# dot_matrix_4A_noGND.net
KiCad netlist of a schematic drawn in EAGLE
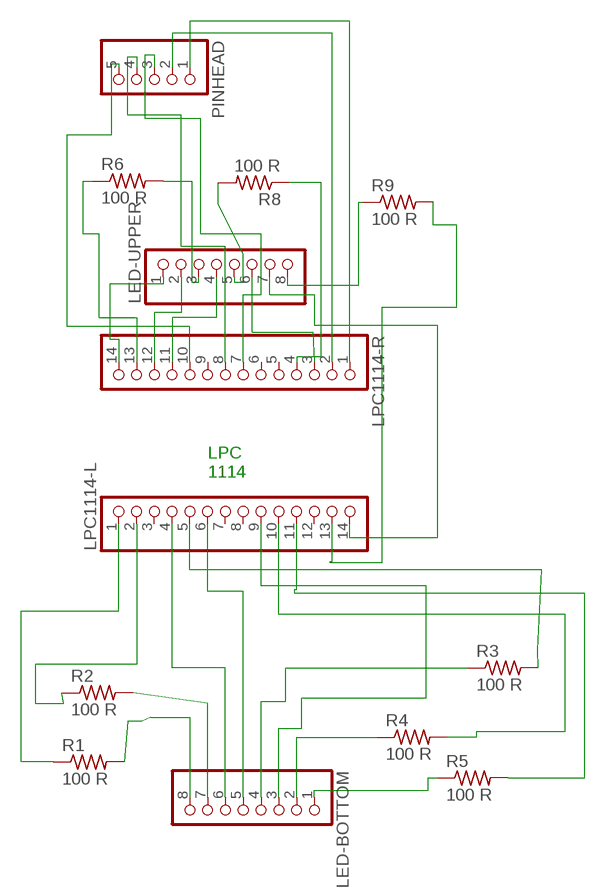
[diagram p0: schematic, sheet 1]

(export (version "E")
  (design (tool "Eeschema 10.0.6"))
  (components
    (comp (ref "LED-BOTTOM")
      (value "PINHD-1X8")
      (footprint "eagle-import:1X08")
      (libsource (lib "eagle-import") (part "PINHD-1X8"))
    )
    (comp (ref "LED-UPPER")
      (value "PINHD-1X8")
      (footprint "eagle-import:1X08")
      (libsource (lib "eagle-import") (part "PINHD-1X8"))
    )
    (comp (ref "LPC1114-L")
      (value "PINHD-1X14")
      (footprint "eagle-import:1X14")
      (libsource (lib "eagle-import") (part "PINHD-1X14"))
    )
    (comp (ref "LPC1114-R")
      (value "PINHD-1X14")
      (footprint "eagle-import:1X14")
      (libsource (lib "eagle-import") (part "PINHD-1X14"))
    )
    (comp (ref "PINHEAD")
      (value "PINHD-1X5")
      (footprint "eagle-import:1X05")
      (libsource (lib "eagle-import") (part "PINHD-1X5"))
    )
    (comp (ref "R1")
      (value "100 R")
      (footprint "eagle-import:0204_7")
      (libsource (lib "eagle-import") (part "R-US_0204/7"))
    )
    (comp (ref "R2")
      (value "100 R")
      (footprint "eagle-import:0204_7")
      (libsource (lib "eagle-import") (part "R-US_0204/7"))
    )
    (comp (ref "R3")
      (value "100 R")
      (footprint "eagle-import:0204_7")
      (libsource (lib "eagle-import") (part "R-US_0204/7"))
    )
    (comp (ref "R4")
      (value "100 R")
      (footprint "eagle-import:0204_7")
      (libsource (lib "eagle-import") (part "R-US_0204/7"))
    )
    (comp (ref "R5")
      (value "100 R")
      (footprint "eagle-import:0204_7")
      (libsource (lib "eagle-import") (part "R-US_0204/7"))
    )
    (comp (ref "R6")
      (value "100 R")
      (footprint "eagle-import:0204_7")
      (libsource (lib "eagle-import") (part "R-US_0204/7"))
    )
    (comp (ref "R8")
      (value "100 R")
      (footprint "eagle-import:0204_7")
      (libsource (lib "eagle-import") (part "R-US_0204/7"))
    )
    (comp (ref "R9")
      (value "100 R")
      (footprint "eagle-import:0204_7")
      (libsource (lib "eagle-import") (part "R-US_0204/7"))
    )
  )
  (nets
    (net (code "1") (name "Net-(LED-BOTTOM-Pad1)") (class "Default")
      (node (ref "LED-BOTTOM") (pin "1") (pinfunction "1_1") (pintype "passive"))
      (node (ref "R5") (pin "1") (pinfunction "1_1") (pintype "passive"))
    )
    (net (code "2") (name "Net-(LED-BOTTOM-Pad2)") (class "Default")
      (node (ref "LED-BOTTOM") (pin "2") (pinfunction "2_2") (pintype "passive"))
      (node (ref "R4") (pin "1") (pinfunction "1_1") (pintype "passive"))
    )
    (net (code "3") (name "Net-(LED-BOTTOM-Pad3)") (class "Default")
      (node (ref "LED-BOTTOM") (pin "3") (pinfunction "3_3") (pintype "passive"))
      (node (ref "LPC1114-L") (pin "9") (pinfunction "9_9") (pintype "passive"))
    )
    (net (code "4") (name "Net-(LED-BOTTOM-Pad4)") (class "Default")
      (node (ref "LED-BOTTOM") (pin "4") (pinfunction "4_4") (pintype "passive"))
      (node (ref "R3") (pin "1") (pinfunction "1_1") (pintype "passive"))
    )
    (net (code "5") (name "Net-(LED-BOTTOM-Pad5)") (class "Default")
      (node (ref "LED-BOTTOM") (pin "5") (pinfunction "5_5") (pintype "passive"))
      (node (ref "LPC1114-L") (pin "6") (pinfunction "6_6") (pintype "passive"))
    )
    (net (code "6") (name "Net-(LED-BOTTOM-Pad6)") (class "Default")
      (node (ref "LED-BOTTOM") (pin "6") (pinfunction "6_6") (pintype "passive"))
      (node (ref "LPC1114-L") (pin "4") (pinfunction "4_4") (pintype "passive"))
    )
    (net (code "7") (name "Net-(LED-BOTTOM-Pad7)") (class "Default")
      (node (ref "LED-BOTTOM") (pin "7") (pinfunction "7_7") (pintype "passive"))
      (node (ref "R2") (pin "2") (pinfunction "2_2") (pintype "passive"))
    )
    (net (code "8") (name "Net-(LED-BOTTOM-Pad8)") (class "Default")
      (node (ref "LED-BOTTOM") (pin "8") (pinfunction "8_8") (pintype "passive"))
      (node (ref "R1") (pin "2") (pinfunction "2_2") (pintype "passive"))
    )
    (net (code "9") (name "Net-(LED-UPPER-Pad1)") (class "Default")
      (node (ref "LED-UPPER") (pin "1") (pinfunction "1_1") (pintype "passive"))
      (node (ref "LPC1114-R") (pin "14") (pinfunction "14_14") (pintype "passive"))
    )
    (net (code "10") (name "Net-(LED-UPPER-Pad2)") (class "Default")
      (node (ref "LED-UPPER") (pin "2") (pinfunction "2_2") (pintype "passive"))
      (node (ref "LPC1114-R") (pin "12") (pinfunction "12_12") (pintype "passive"))
    )
    (net (code "11") (name "Net-(LED-UPPER-Pad3)") (class "Default")
      (node (ref "LED-UPPER") (pin "3") (pinfunction "3_3") (pintype "passive"))
      (node (ref "R6") (pin "2") (pinfunction "2_2") (pintype "passive"))
    )
    (net (code "12") (name "Net-(LED-UPPER-Pad4)") (class "Default")
      (node (ref "LED-UPPER") (pin "4") (pinfunction "4_4") (pintype "passive"))
      (node (ref "LPC1114-R") (pin "11") (pinfunction "11_11") (pintype "passive"))
    )
    (net (code "13") (name "Net-(LED-UPPER-Pad5)") (class "Default")
      (node (ref "LED-UPPER") (pin "5") (pinfunction "5_5") (pintype "passive"))
      (node (ref "R8") (pin "2") (pinfunction "2_2") (pintype "passive"))
    )
    (net (code "14") (name "Net-(LED-UPPER-Pad6)") (class "Default")
      (node (ref "LED-UPPER") (pin "6") (pinfunction "6_6") (pintype "passive"))
      (node (ref "LPC1114-R") (pin "3") (pinfunction "3_3") (pintype "passive"))
    )
    (net (code "15") (name "Net-(LED-UPPER-Pad7)") (class "Default")
      (node (ref "LED-UPPER") (pin "7") (pinfunction "7_7") (pintype "passive"))
      (node (ref "LPC1114-L") (pin "14") (pinfunction "14_14") (pintype "passive"))
    )
    (net (code "16") (name "Net-(LED-UPPER-Pad8)") (class "Default")
      (node (ref "LED-UPPER") (pin "8") (pinfunction "8_8") (pintype "passive"))
      (node (ref "R9") (pin "1") (pinfunction "1_1") (pintype "passive"))
    )
    (net (code "17") (name "Net-(LPC1114-L-Pad1)") (class "Default")
      (node (ref "LPC1114-L") (pin "1") (pinfunction "1_1") (pintype "passive"))
      (node (ref "R1") (pin "1") (pinfunction "1_1") (pintype "passive"))
    )
    (net (code "18") (name "Net-(LPC1114-L-Pad2)") (class "Default")
      (node (ref "LPC1114-L") (pin "2") (pinfunction "2_2") (pintype "passive"))
      (node (ref "R2") (pin "1") (pinfunction "1_1") (pintype "passive"))
    )
    (net (code "19") (name "Net-(LPC1114-L-Pad5)") (class "Default")
      (node (ref "LPC1114-L") (pin "5") (pinfunction "5_5") (pintype "passive"))
      (node (ref "R3") (pin "2") (pinfunction "2_2") (pintype "passive"))
    )
    (net (code "20") (name "Net-(LPC1114-L-Pad10)") (class "Default")
      (node (ref "LPC1114-L") (pin "10") (pinfunction "10_10") (pintype "passive"))
      (node (ref "R4") (pin "2") (pinfunction "2_2") (pintype "passive"))
    )
    (net (code "21") (name "Net-(LPC1114-L-Pad11)") (class "Default")
      (node (ref "LPC1114-L") (pin "11") (pinfunction "11_11") (pintype "passive"))
      (node (ref "R5") (pin "2") (pinfunction "2_2") (pintype "passive"))
    )
    (net (code "22") (name "Net-(LPC1114-L-Pad13)") (class "Default")
      (node (ref "LPC1114-L") (pin "13") (pinfunction "13_13") (pintype "passive"))
      (node (ref "R9") (pin "2") (pinfunction "2_2") (pintype "passive"))
    )
    (net (code "23") (name "Net-(LPC1114-R-Pad1)") (class "Default")
      (node (ref "LPC1114-R") (pin "1") (pinfunction "1_1") (pintype "passive"))
      (node (ref "PINHEAD") (pin "1") (pinfunction "1_1") (pintype "passive"))
    )
    (net (code "24") (name "Net-(LPC1114-R-Pad2)") (class "Default")
      (node (ref "LPC1114-R") (pin "2") (pinfunction "2_2") (pintype "passive"))
      (node (ref "PINHEAD") (pin "2") (pinfunction "2_2") (pintype "passive"))
    )
    (net (code "25") (name "Net-(LPC1114-R-Pad4)") (class "Default")
      (node (ref "LPC1114-R") (pin "4") (pinfunction "4_4") (pintype "passive"))
      (node (ref "R8") (pin "1") (pinfunction "1_1") (pintype "passive"))
    )
    (net (code "26") (name "Net-(LPC1114-R-Pad7)") (class "Default")
      (node (ref "LPC1114-R") (pin "7") (pinfunction "7_7") (pintype "passive"))
      (node (ref "PINHEAD") (pin "3") (pinfunction "3_3") (pintype "passive"))
    )
    (net (code "27") (name "Net-(LPC1114-R-Pad8)") (class "Default")
      (node (ref "LPC1114-R") (pin "8") (pinfunction "8_8") (pintype "passive"))
      (node (ref "PINHEAD") (pin "4") (pinfunction "4_4") (pintype "passive"))
    )
    (net (code "28") (name "Net-(LPC1114-R-Pad10)") (class "Default")
      (node (ref "LPC1114-R") (pin "10") (pinfunction "10_10") (pintype "passive"))
      (node (ref "PINHEAD") (pin "5") (pinfunction "5_5") (pintype "passive"))
    )
    (net (code "29") (name "Net-(LPC1114-R-Pad13)") (class "Default")
      (node (ref "LPC1114-R") (pin "13") (pinfunction "13_13") (pintype "passive"))
      (node (ref "R6") (pin "1") (pinfunction "1_1") (pintype "passive"))
    )
    (net (code "30") (name "unconnected-(LPC1114-L-Pad3)") (class "Default")
      (node (ref "LPC1114-L") (pin "3") (pinfunction "3_3") (pintype "passive"))
    )
    (net (code "31") (name "unconnected-(LPC1114-L-Pad7)") (class "Default")
      (node (ref "LPC1114-L") (pin "7") (pinfunction "7_7") (pintype "passive"))
    )
    (net (code "32") (name "unconnected-(LPC1114-L-Pad8)") (class "Default")
      (node (ref "LPC1114-L") (pin "8") (pinfunction "8_8") (pintype "passive"))
    )
    (net (code "33") (name "unconnected-(LPC1114-L-Pad12)") (class "Default")
      (node (ref "LPC1114-L") (pin "12") (pinfunction "12_12") (pintype "passive"))
    )
    (net (code "34") (name "unconnected-(LPC1114-R-Pad5)") (class "Default")
      (node (ref "LPC1114-R") (pin "5") (pinfunction "5_5") (pintype "passive"))
    )
    (net (code "35") (name "unconnected-(LPC1114-R-Pad6)") (class "Default")
      (node (ref "LPC1114-R") (pin "6") (pinfunction "6_6") (pintype "passive"))
    )
    (net (code "36") (name "unconnected-(LPC1114-R-Pad9)") (class "Default")
      (node (ref "LPC1114-R") (pin "9") (pinfunction "9_9") (pintype "passive"))
    )
  )
)
